# PixiFlood_20w.net
KiCad netlist of a schematic drawn in EAGLE
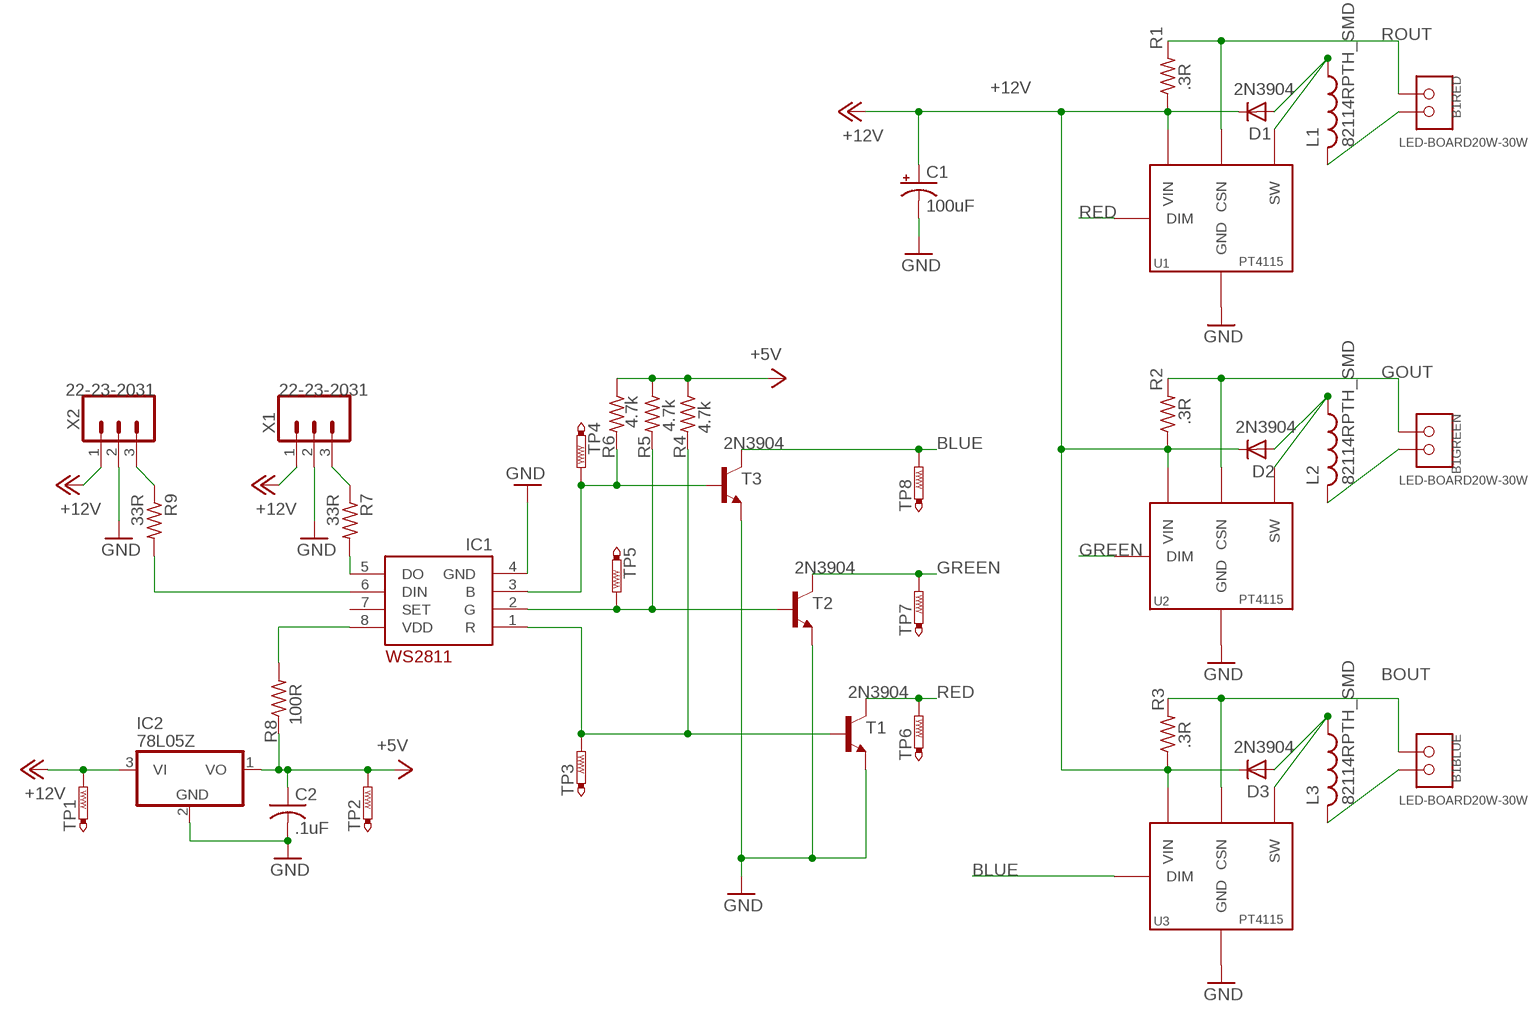
[diagram p0: schematic, sheet 1]

(export (version "E")
  (design (tool "Eeschema 10.0.6"))
  (components
    (comp (ref "B1")
      (value "LED-BOARD20W-30W")
      (footprint "eagle-import:LED-BOARD-LRG")
      (libsource (lib "eagle-import") (part "LED-BOARD20W-30W"))
    )
    (comp (ref "C1")
      (value "100uF")
      (footprint "eagle-import:TT2D6L")
      (libsource (lib "eagle-import") (part "CPOL-USTT2D6L"))
    )
    (comp (ref "C2")
      (value ".1uF")
      (footprint "eagle-import:C050-024X044")
      (libsource (lib "eagle-import") (part "C-US050-024X044"))
    )
    (comp (ref "D1")
      (value "2N3904")
      (footprint "eagle-import:DO07")
      (libsource (lib "eagle-import") (part "DIODE-DO07"))
    )
    (comp (ref "D2")
      (value "2N3904")
      (footprint "eagle-import:DO07")
      (libsource (lib "eagle-import") (part "DIODE-DO07"))
    )
    (comp (ref "D3")
      (value "2N3904")
      (footprint "eagle-import:DO07")
      (libsource (lib "eagle-import") (part "DIODE-DO07"))
    )
    (comp (ref "IC1")
      (value "WS2811-SOP8")
      (footprint "eagle-import:SO08-SKINNYPADS")
      (libsource (lib "eagle-import") (part "WS2811-SOP8"))
    )
    (comp (ref "IC2")
      (value "78L05Z")
      (footprint "eagle-import:TO92")
      (libsource (lib "eagle-import") (part "78ZL05"))
    )
    (comp (ref "L1")
      (value "82114RPTH_SMD")
      (footprint "eagle-import:INDUCTOR")
      (libsource (lib "eagle-import") (part "82114RPTH_SMD"))
    )
    (comp (ref "L2")
      (value "82114RPTH_SMD")
      (footprint "eagle-import:INDUCTOR")
      (libsource (lib "eagle-import") (part "82114RPTH_SMD"))
    )
    (comp (ref "L3")
      (value "82114RPTH_SMD")
      (footprint "eagle-import:INDUCTOR")
      (libsource (lib "eagle-import") (part "82114RPTH_SMD"))
    )
    (comp (ref "R1")
      (value ".3R")
      (footprint "eagle-import:0204_7")
      (libsource (lib "eagle-import") (part "resistor_R-US_0204/7"))
    )
    (comp (ref "R2")
      (value ".3R")
      (footprint "eagle-import:0204_7")
      (libsource (lib "eagle-import") (part "resistor_R-US_0204/7"))
    )
    (comp (ref "R3")
      (value ".3R")
      (footprint "eagle-import:0204_7")
      (libsource (lib "eagle-import") (part "resistor_R-US_0204/7"))
    )
    (comp (ref "R4")
      (value "4.7k")
      (footprint "eagle-import:0204_7")
      (libsource (lib "eagle-import") (part "resistor_R-US_0204/7"))
    )
    (comp (ref "R5")
      (value "4.7k")
      (footprint "eagle-import:0204_7")
      (libsource (lib "eagle-import") (part "resistor_R-US_0204/7"))
    )
    (comp (ref "R6")
      (value "4.7k")
      (footprint "eagle-import:0204_7")
      (libsource (lib "eagle-import") (part "resistor_R-US_0204/7"))
    )
    (comp (ref "R7")
      (value "33R")
      (footprint "eagle-import:0204_7")
      (libsource (lib "eagle-import") (part "R-US_0204/7"))
    )
    (comp (ref "R8")
      (value "100R")
      (footprint "eagle-import:0204_7")
      (libsource (lib "eagle-import") (part "R-US_0204/7"))
    )
    (comp (ref "R9")
      (value "33R")
      (footprint "eagle-import:0204_7")
      (libsource (lib "eagle-import") (part "R-US_0204/7"))
    )
    (comp (ref "T1")
      (value "2N3904")
      (footprint "eagle-import:TO92")
      (libsource (lib "eagle-import") (part "2N3904"))
    )
    (comp (ref "T2")
      (value "2N3904")
      (footprint "eagle-import:TO92")
      (libsource (lib "eagle-import") (part "2N3904"))
    )
    (comp (ref "T3")
      (value "2N3904")
      (footprint "eagle-import:TO92")
      (libsource (lib "eagle-import") (part "2N3904"))
    )
    (comp (ref "TP1")
      (value "PTR1B2,54")
      (footprint "eagle-import:B2,54")
      (libsource (lib "eagle-import") (part "PTR1B2,54"))
    )
    (comp (ref "TP2")
      (value "PTR1B2,54")
      (footprint "eagle-import:B2,54")
      (libsource (lib "eagle-import") (part "PTR1B2,54"))
    )
    (comp (ref "TP3")
      (value "PTR1B1,27")
      (footprint "eagle-import:B1,27")
      (libsource (lib "eagle-import") (part "PTR1B1,27"))
    )
    (comp (ref "TP4")
      (value "PTR1B1,27")
      (footprint "eagle-import:B1,27")
      (libsource (lib "eagle-import") (part "PTR1B1,27"))
    )
    (comp (ref "TP5")
      (value "PTR1B1,27")
      (footprint "eagle-import:B1,27")
      (libsource (lib "eagle-import") (part "PTR1B1,27"))
    )
    (comp (ref "TP6")
      (value "PTR1B1,27")
      (footprint "eagle-import:B1,27")
      (libsource (lib "eagle-import") (part "PTR1B1,27"))
    )
    (comp (ref "TP7")
      (value "PTR1B1,27")
      (footprint "eagle-import:B1,27")
      (libsource (lib "eagle-import") (part "PTR1B1,27"))
    )
    (comp (ref "TP8")
      (value "PTR1B1,27")
      (footprint "eagle-import:B1,27")
      (libsource (lib "eagle-import") (part "PTR1B1,27"))
    )
    (comp (ref "U1")
      (value "PT4115B89E")
      (footprint "eagle-import:SOT89-5")
      (libsource (lib "eagle-import") (part "PT4115B89E"))
    )
    (comp (ref "U2")
      (value "PT4115B89E")
      (footprint "eagle-import:SOT89-5")
      (libsource (lib "eagle-import") (part "PT4115B89E"))
    )
    (comp (ref "U3")
      (value "PT4115B89E")
      (footprint "eagle-import:SOT89-5")
      (libsource (lib "eagle-import") (part "PT4115B89E"))
    )
    (comp (ref "X1")
      (value "22-23-2031")
      (footprint "eagle-import:22-23-2031")
      (fields (field (name "MF") "MOLEX"))
      (libsource (lib "eagle-import") (part "22-23-2031"))
    )
    (comp (ref "X2")
      (value "22-23-2031")
      (footprint "eagle-import:22-23-2031")
      (fields (field (name "MF") "MOLEX"))
      (libsource (lib "eagle-import") (part "22-23-2031"))
    )
  )
  (nets
    (net (code "1") (name "+5V") (class "Default")
      (node (ref "C2") (pin "1") (pinfunction "1_1") (pintype "passive"))
      (node (ref "IC2") (pin "1") (pinfunction "VO_1") (pintype "passive"))
      (node (ref "R4") (pin "1") (pinfunction "1_1") (pintype "passive"))
      (node (ref "R5") (pin "1") (pinfunction "1_1") (pintype "passive"))
      (node (ref "R6") (pin "1") (pinfunction "1_1") (pintype "passive"))
      (node (ref "R8") (pin "1") (pinfunction "1_1") (pintype "passive"))
      (node (ref "TP2") (pin "TP") (pinfunction "TP_TP") (pintype "input"))
    )
    (net (code "2") (name "+12V") (class "Default")
      (node (ref "C1") (pin "+") (pinfunction "+_+") (pintype "passive"))
      (node (ref "D1") (pin "C") (pinfunction "C_C") (pintype "passive"))
      (node (ref "D2") (pin "C") (pinfunction "C_C") (pintype "passive"))
      (node (ref "D3") (pin "C") (pinfunction "C_C") (pintype "passive"))
      (node (ref "IC2") (pin "3") (pinfunction "VI_3") (pintype "input"))
      (node (ref "R1") (pin "1") (pinfunction "1_1") (pintype "passive"))
      (node (ref "R2") (pin "1") (pinfunction "1_1") (pintype "passive"))
      (node (ref "R3") (pin "1") (pinfunction "1_1") (pintype "passive"))
      (node (ref "TP1") (pin "TP") (pinfunction "TP_TP") (pintype "input"))
      (node (ref "U1") (pin "5") (pinfunction "VIN_5") (pintype "power_in"))
      (node (ref "U2") (pin "5") (pinfunction "VIN_5") (pintype "power_in"))
      (node (ref "U3") (pin "5") (pinfunction "VIN_5") (pintype "power_in"))
      (node (ref "X1") (pin "1") (pinfunction "1_1") (pintype "passive"))
      (node (ref "X2") (pin "1") (pinfunction "1_1") (pintype "passive"))
    )
    (net (code "3") (name "/BLUE") (class "Default")
      (node (ref "T3") (pin "1") (pinfunction "C_1") (pintype "passive"))
      (node (ref "TP8") (pin "TP") (pinfunction "TP_TP") (pintype "input"))
      (node (ref "U3") (pin "3") (pinfunction "DIM_3") (pintype "bidirectional"))
    )
    (net (code "4") (name "/BOUT") (class "Default")
      (node (ref "B1") (pin "B+") (pinfunction "P$2_B+") (pintype "bidirectional"))
      (node (ref "B1") (pin "B+@2") (pinfunction "P$2_B+@2") (pintype "bidirectional"))
      (node (ref "R3") (pin "2") (pinfunction "2_2") (pintype "passive"))
      (node (ref "U3") (pin "4") (pinfunction "CSN_4") (pintype "bidirectional"))
    )
    (net (code "5") (name "/GOUT") (class "Default")
      (node (ref "B1") (pin "G+") (pinfunction "P$2_G+") (pintype "bidirectional"))
      (node (ref "B1") (pin "G+@1") (pinfunction "P$2_G+@1") (pintype "bidirectional"))
      (node (ref "R2") (pin "2") (pinfunction "2_2") (pintype "passive"))
      (node (ref "U2") (pin "4") (pinfunction "CSN_4") (pintype "bidirectional"))
    )
    (net (code "6") (name "/GREEN") (class "Default")
      (node (ref "T2") (pin "1") (pinfunction "C_1") (pintype "passive"))
      (node (ref "TP7") (pin "TP") (pinfunction "TP_TP") (pintype "input"))
      (node (ref "U2") (pin "3") (pinfunction "DIM_3") (pintype "bidirectional"))
    )
    (net (code "7") (name "/RED") (class "Default")
      (node (ref "T1") (pin "1") (pinfunction "C_1") (pintype "passive"))
      (node (ref "TP6") (pin "TP") (pinfunction "TP_TP") (pintype "input"))
      (node (ref "U1") (pin "3") (pinfunction "DIM_3") (pintype "bidirectional"))
    )
    (net (code "8") (name "/ROUT") (class "Default")
      (node (ref "B1") (pin "R+") (pinfunction "P$2_R+") (pintype "bidirectional"))
      (node (ref "B1") (pin "R+@1") (pinfunction "P$2_R+@1") (pintype "bidirectional"))
      (node (ref "R1") (pin "2") (pinfunction "2_2") (pintype "passive"))
      (node (ref "U1") (pin "4") (pinfunction "CSN_4") (pintype "bidirectional"))
    )
    (net (code "9") (name "GND") (class "Default")
      (node (ref "C1") (pin "-") (pinfunction "-_-") (pintype "passive"))
      (node (ref "C2") (pin "2") (pinfunction "2_2") (pintype "passive"))
      (node (ref "IC1") (pin "4") (pinfunction "GND_4") (pintype "power_in"))
      (node (ref "IC2") (pin "2") (pinfunction "GND_2") (pintype "passive"))
      (node (ref "T1") (pin "3") (pinfunction "E_3") (pintype "passive"))
      (node (ref "T2") (pin "3") (pinfunction "E_3") (pintype "passive"))
      (node (ref "T3") (pin "3") (pinfunction "E_3") (pintype "passive"))
      (node (ref "U1") (pin "2") (pinfunction "GND_2") (pintype "power_in"))
      (node (ref "U1") (pin "2@1") (pinfunction "GND_2@1") (pintype "power_in"))
      (node (ref "U1") (pin "2@2") (pinfunction "GND_2@2") (pintype "power_in"))
      (node (ref "U1") (pin "2@3") (pinfunction "GND_2@3") (pintype "power_in"))
      (node (ref "U2") (pin "2") (pinfunction "GND_2") (pintype "power_in"))
      (node (ref "U2") (pin "2@1") (pinfunction "GND_2@1") (pintype "power_in"))
      (node (ref "U2") (pin "2@2") (pinfunction "GND_2@2") (pintype "power_in"))
      (node (ref "U2") (pin "2@3") (pinfunction "GND_2@3") (pintype "power_in"))
      (node (ref "U3") (pin "2") (pinfunction "GND_2") (pintype "power_in"))
      (node (ref "U3") (pin "2@1") (pinfunction "GND_2@1") (pintype "power_in"))
      (node (ref "U3") (pin "2@2") (pinfunction "GND_2@2") (pintype "power_in"))
      (node (ref "U3") (pin "2@3") (pinfunction "GND_2@3") (pintype "power_in"))
      (node (ref "X1") (pin "2") (pinfunction "2_2") (pintype "passive"))
      (node (ref "X2") (pin "2") (pinfunction "2_2") (pintype "passive"))
    )
    (net (code "10") (name "Net-(B1A-P$1-PadB-)") (class "Default")
      (node (ref "B1") (pin "B-") (pinfunction "P$1_B-") (pintype "bidirectional"))
      (node (ref "B1") (pin "B-@1") (pinfunction "P$1_B-@1") (pintype "bidirectional"))
      (node (ref "L3") (pin "2") (pinfunction "2_2") (pintype "passive"))
      (node (ref "L3") (pin "2@A") (pinfunction "2_2@A") (pintype "passive"))
    )
    (net (code "11") (name "Net-(B1B-P$1-PadG-)") (class "Default")
      (node (ref "B1") (pin "G-") (pinfunction "P$1_G-") (pintype "bidirectional"))
      (node (ref "B1") (pin "G-@1") (pinfunction "P$1_G-@1") (pintype "bidirectional"))
      (node (ref "L2") (pin "2") (pinfunction "2_2") (pintype "passive"))
      (node (ref "L2") (pin "2@A") (pinfunction "2_2@A") (pintype "passive"))
    )
    (net (code "12") (name "Net-(B1C-P$1-PadR-)") (class "Default")
      (node (ref "B1") (pin "R-") (pinfunction "P$1_R-") (pintype "bidirectional"))
      (node (ref "B1") (pin "R-@1") (pinfunction "P$1_R-@1") (pintype "bidirectional"))
      (node (ref "L1") (pin "2") (pinfunction "2_2") (pintype "passive"))
      (node (ref "L1") (pin "2@A") (pinfunction "2_2@A") (pintype "passive"))
    )
    (net (code "13") (name "Net-(IC1-B)") (class "Default")
      (node (ref "IC1") (pin "3") (pinfunction "B_3") (pintype "open_collector"))
      (node (ref "R6") (pin "2") (pinfunction "2_2") (pintype "passive"))
      (node (ref "T3") (pin "2") (pinfunction "B_2") (pintype "passive"))
      (node (ref "TP4") (pin "TP") (pinfunction "TP_TP") (pintype "input"))
    )
    (net (code "14") (name "Net-(IC1-DIN)") (class "Default")
      (node (ref "IC1") (pin "6") (pinfunction "DIN_6") (pintype "input"))
      (node (ref "R9") (pin "2") (pinfunction "2_2") (pintype "passive"))
    )
    (net (code "15") (name "Net-(IC1-DO)") (class "Default")
      (node (ref "IC1") (pin "5") (pinfunction "DO_5") (pintype "output"))
      (node (ref "R7") (pin "2") (pinfunction "2_2") (pintype "passive"))
    )
    (net (code "16") (name "Net-(IC1-G)") (class "Default")
      (node (ref "IC1") (pin "2") (pinfunction "G_2") (pintype "open_collector"))
      (node (ref "R5") (pin "2") (pinfunction "2_2") (pintype "passive"))
      (node (ref "T2") (pin "2") (pinfunction "B_2") (pintype "passive"))
      (node (ref "TP5") (pin "TP") (pinfunction "TP_TP") (pintype "input"))
    )
    (net (code "17") (name "Net-(IC1-R)") (class "Default")
      (node (ref "IC1") (pin "1") (pinfunction "R_1") (pintype "open_collector"))
      (node (ref "R4") (pin "2") (pinfunction "2_2") (pintype "passive"))
      (node (ref "T1") (pin "2") (pinfunction "B_2") (pintype "passive"))
      (node (ref "TP3") (pin "TP") (pinfunction "TP_TP") (pintype "input"))
    )
    (net (code "18") (name "Net-(IC1-VDD)") (class "Default")
      (node (ref "IC1") (pin "8") (pinfunction "VDD_8") (pintype "power_in"))
      (node (ref "R8") (pin "2") (pinfunction "2_2") (pintype "passive"))
    )
    (net (code "19") (name "Net-(R7-Pad1)") (class "Default")
      (node (ref "R7") (pin "1") (pinfunction "1_1") (pintype "passive"))
      (node (ref "X1") (pin "3") (pinfunction "3_3") (pintype "passive"))
    )
    (net (code "20") (name "Net-(R9-Pad1)") (class "Default")
      (node (ref "R9") (pin "1") (pinfunction "1_1") (pintype "passive"))
      (node (ref "X2") (pin "3") (pinfunction "3_3") (pintype "passive"))
    )
    (net (code "21") (name "Net-(U1-SW)") (class "Default")
      (node (ref "D1") (pin "A") (pinfunction "A_A") (pintype "passive"))
      (node (ref "L1") (pin "1") (pinfunction "1_1") (pintype "passive"))
      (node (ref "L1") (pin "1@A") (pinfunction "1_1@A") (pintype "passive"))
      (node (ref "U1") (pin "1") (pinfunction "SW_1") (pintype "bidirectional"))
    )
    (net (code "22") (name "Net-(U2-SW)") (class "Default")
      (node (ref "D2") (pin "A") (pinfunction "A_A") (pintype "passive"))
      (node (ref "L2") (pin "1") (pinfunction "1_1") (pintype "passive"))
      (node (ref "L2") (pin "1@A") (pinfunction "1_1@A") (pintype "passive"))
      (node (ref "U2") (pin "1") (pinfunction "SW_1") (pintype "bidirectional"))
    )
    (net (code "23") (name "Net-(U3-SW)") (class "Default")
      (node (ref "D3") (pin "A") (pinfunction "A_A") (pintype "passive"))
      (node (ref "L3") (pin "1") (pinfunction "1_1") (pintype "passive"))
      (node (ref "L3") (pin "1@A") (pinfunction "1_1@A") (pintype "passive"))
      (node (ref "U3") (pin "1") (pinfunction "SW_1") (pintype "bidirectional"))
    )
    (net (code "24") (name "unconnected-(IC1-SET-Pad7)") (class "Default")
      (node (ref "IC1") (pin "7") (pinfunction "SET_7") (pintype "input"))
    )
  )
)
